# client.net
KiCad netlist of a schematic drawn in EAGLE
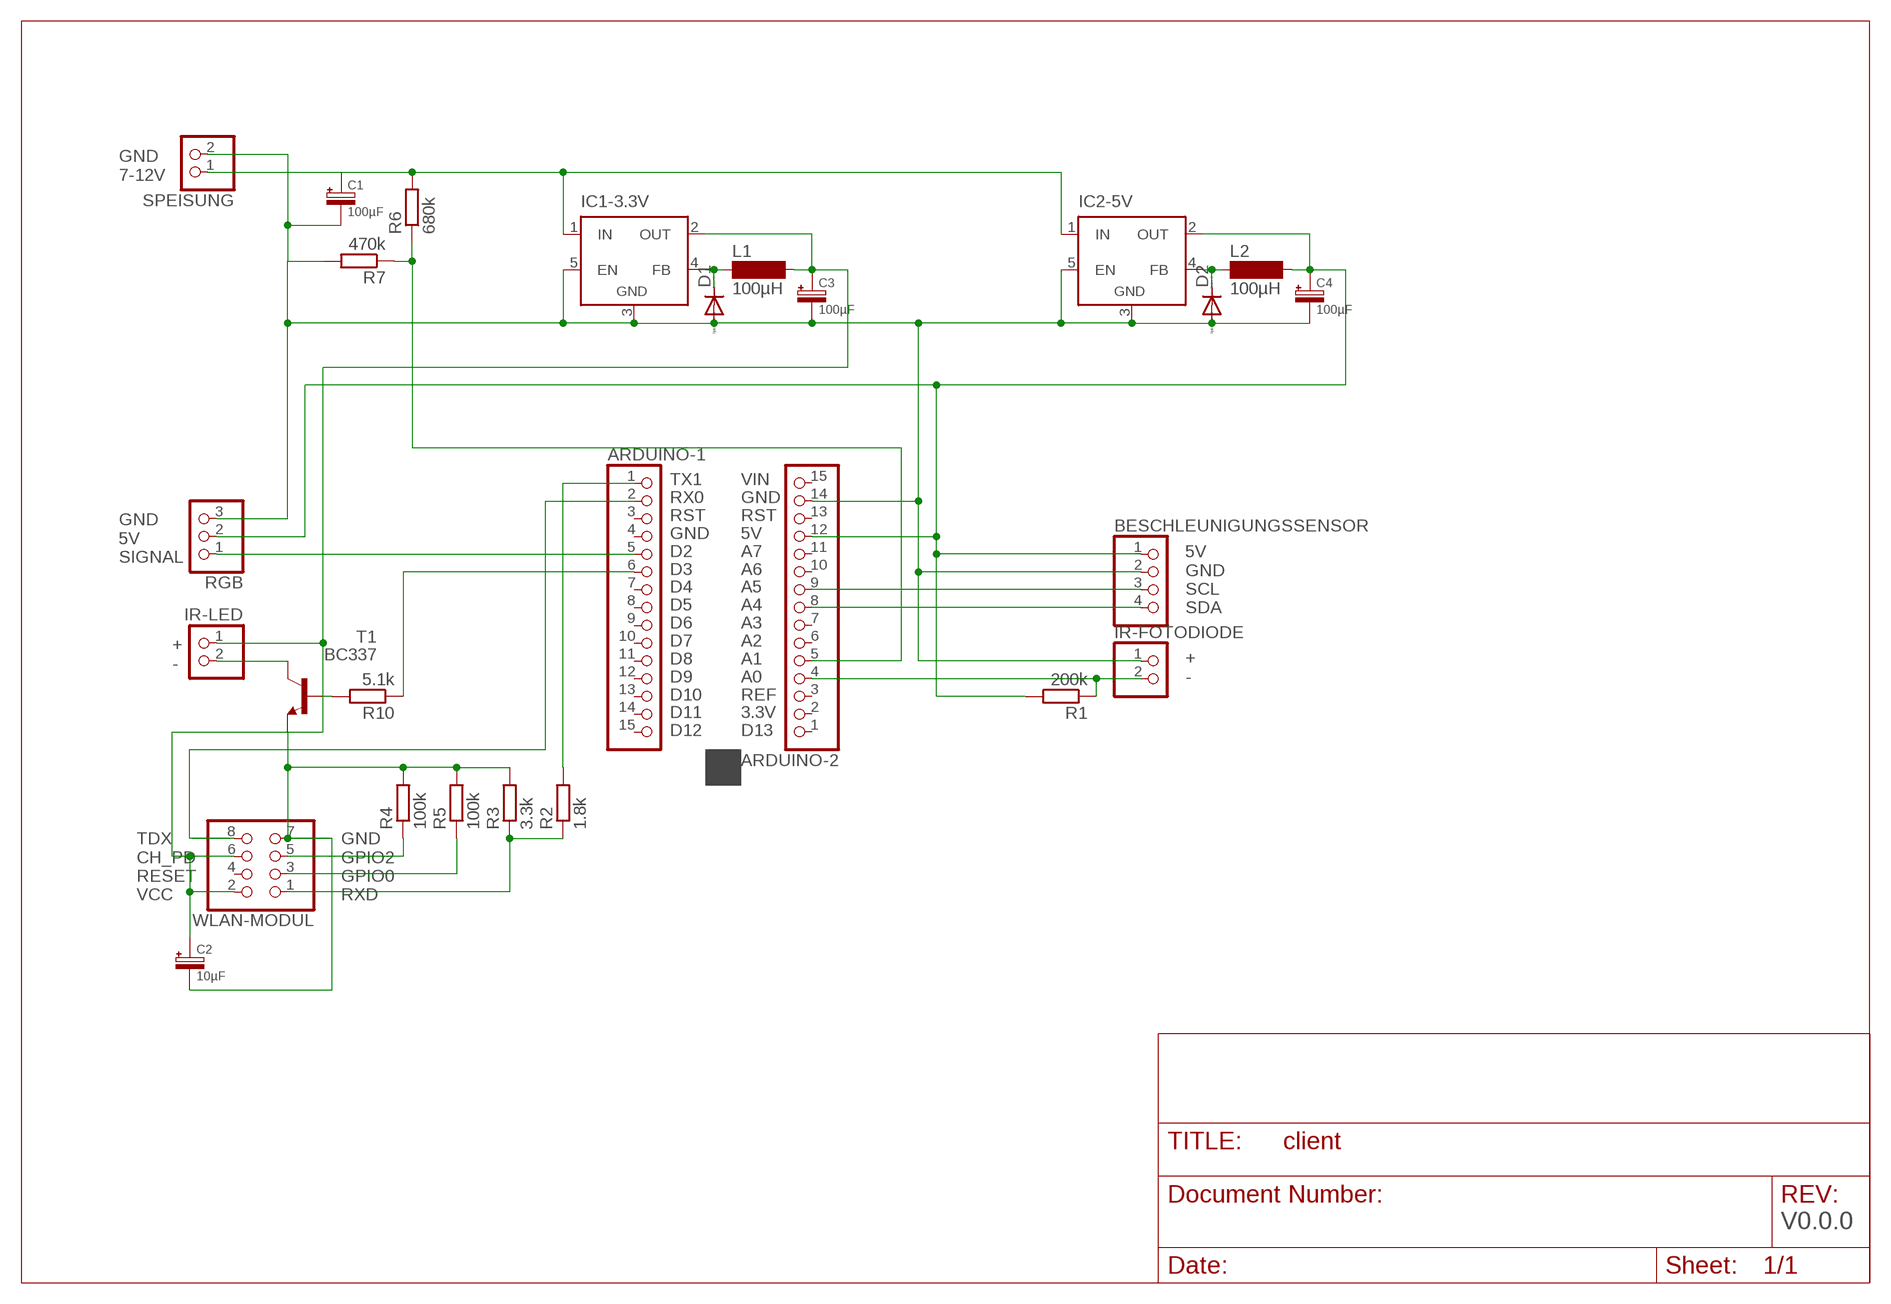
[diagram p0: schematic, sheet 1]

(export (version "E")
  (design (tool "Eeschema 10.0.6"))
  (components
    (comp (ref "ARDUINO-1")
      (value "PINHD-1X15")
      (footprint "eagle-import:1X15")
      (libsource (lib "eagle-import") (part "PINHD-1X15"))
    )
    (comp (ref "ARDUINO-2")
      (value "PINHD-1X15")
      (footprint "eagle-import:1X15")
      (libsource (lib "eagle-import") (part "PINHD-1X15"))
    )
    (comp (ref "BESCHLEUNIGUNGSSENSOR")
      (value "PINHD-1X4")
      (footprint "eagle-import:1X04")
      (libsource (lib "eagle-import") (part "PINHD-1X4"))
    )
    (comp (ref "C1")
      (value "100µF")
      (footprint "eagle-import:KONDENSATOR_ELEKTROLYT")
      (libsource (lib "eagle-import") (part "KONDENSATOR_ELEKTROLYT"))
    )
    (comp (ref "C2")
      (value "10µF")
      (footprint "eagle-import:KONDENSATOR_ELEKTROLYT")
      (libsource (lib "eagle-import") (part "KONDENSATOR_ELEKTROLYT"))
    )
    (comp (ref "C3")
      (value "100µF")
      (footprint "eagle-import:KONDENSATOR_ELEKTROLYT")
      (libsource (lib "eagle-import") (part "KONDENSATOR_ELEKTROLYT"))
    )
    (comp (ref "C4")
      (value "100µF")
      (footprint "eagle-import:KONDENSATOR_ELEKTROLYT")
      (libsource (lib "eagle-import") (part "KONDENSATOR_ELEKTROLYT"))
    )
    (comp (ref "D1")
      (value "DIODE-D-2.5")
      (footprint "eagle-import:D-2.5")
      (libsource (lib "eagle-import") (part "DIODE-D-2.5"))
    )
    (comp (ref "D2")
      (value "DIODE-D-2.5")
      (footprint "eagle-import:D-2.5")
      (libsource (lib "eagle-import") (part "DIODE-D-2.5"))
    )
    (comp (ref "IC1-3.3V")
      (value "LM2596TV")
      (footprint "eagle-import:TO220-51")
      (libsource (lib "eagle-import") (part "LM2596TV"))
    )
    (comp (ref "IC2-5V")
      (value "LM2596TV")
      (footprint "eagle-import:TO220-51")
      (libsource (lib "eagle-import") (part "LM2596TV"))
    )
    (comp (ref "IR-FOTODIODE")
      (value "PINHD-1X2")
      (footprint "eagle-import:1X02")
      (libsource (lib "eagle-import") (part "PINHD-1X2"))
    )
    (comp (ref "IR-LED")
      (value "PINHD-1X2")
      (footprint "eagle-import:1X02")
      (libsource (lib "eagle-import") (part "PINHD-1X2"))
    )
    (comp (ref "L1")
      (value "100µH")
      (footprint "eagle-import:SM-L15A")
      (libsource (lib "eagle-import") (part "SM-L15A"))
    )
    (comp (ref "L2")
      (value "100µH")
      (footprint "eagle-import:SM-L15A")
      (libsource (lib "eagle-import") (part "SM-L15A"))
    )
    (comp (ref "R1")
      (value "200k")
      (footprint "eagle-import:0204V")
      (libsource (lib "eagle-import") (part "rcl_334_R-EU_0204/2V"))
    )
    (comp (ref "R2")
      (value "1.8k")
      (footprint "eagle-import:0207_10")
      (libsource (lib "eagle-import") (part "R-EU_0207/10"))
    )
    (comp (ref "R3")
      (value "3.3k")
      (footprint "eagle-import:0207_10")
      (libsource (lib "eagle-import") (part "R-EU_0207/10"))
    )
    (comp (ref "R4")
      (value "100k")
      (footprint "eagle-import:0207_10")
      (libsource (lib "eagle-import") (part "R-EU_0207/10"))
    )
    (comp (ref "R5")
      (value "100k")
      (footprint "eagle-import:0207_10")
      (libsource (lib "eagle-import") (part "R-EU_0207/10"))
    )
    (comp (ref "R6")
      (value "680k")
      (footprint "eagle-import:0204V")
      (libsource (lib "eagle-import") (part "rcl_334_R-EU_0204/2V"))
    )
    (comp (ref "R7")
      (value "470k")
      (footprint "eagle-import:0204V")
      (libsource (lib "eagle-import") (part "rcl_334_R-EU_0204/2V"))
    )
    (comp (ref "R10")
      (value "5.1k")
      (footprint "eagle-import:0204V")
      (libsource (lib "eagle-import") (part "resistor_R-EU_0204/2V"))
    )
    (comp (ref "RGB")
      (value "PINHD-1X3")
      (footprint "eagle-import:1X03")
      (libsource (lib "eagle-import") (part "PINHD-1X3"))
    )
    (comp (ref "SPEISUNG")
      (value "PINHD-1X2")
      (footprint "eagle-import:1X02")
      (libsource (lib "eagle-import") (part "PINHD-1X2"))
    )
    (comp (ref "T1")
      (value "BC337")
      (footprint "eagle-import:TO92")
      (libsource (lib "eagle-import") (part "BC337"))
    )
    (comp (ref "WLAN-MODUL")
      (value "PINHD-2X4")
      (footprint "eagle-import:2X04")
      (libsource (lib "eagle-import") (part "PINHD-2X4"))
    )
  )
  (nets
    (net (code "1") (name "Net-(ARDUINO-1-Pad1)") (class "Default")
      (node (ref "ARDUINO-1") (pin "1") (pinfunction "1_1") (pintype "passive"))
      (node (ref "R2") (pin "2") (pinfunction "2_2") (pintype "passive"))
    )
    (net (code "2") (name "Net-(ARDUINO-1-Pad2)") (class "Default")
      (node (ref "ARDUINO-1") (pin "2") (pinfunction "2_2") (pintype "passive"))
      (node (ref "WLAN-MODUL") (pin "8") (pinfunction "8_8") (pintype "passive"))
    )
    (net (code "3") (name "Net-(ARDUINO-1-Pad5)") (class "Default")
      (node (ref "ARDUINO-1") (pin "5") (pinfunction "5_5") (pintype "passive"))
      (node (ref "RGB") (pin "1") (pinfunction "1_1") (pintype "passive"))
    )
    (net (code "4") (name "Net-(ARDUINO-1-Pad6)") (class "Default")
      (node (ref "ARDUINO-1") (pin "6") (pinfunction "6_6") (pintype "passive"))
      (node (ref "R10") (pin "1") (pinfunction "1_1") (pintype "passive"))
    )
    (net (code "5") (name "Net-(ARDUINO-2-Pad4)") (class "Default")
      (node (ref "ARDUINO-2") (pin "4") (pinfunction "4_4") (pintype "passive"))
      (node (ref "IR-FOTODIODE") (pin "2") (pinfunction "2_2") (pintype "passive"))
      (node (ref "R1") (pin "1") (pinfunction "1_1") (pintype "passive"))
    )
    (net (code "6") (name "Net-(ARDUINO-2-Pad5)") (class "Default")
      (node (ref "ARDUINO-2") (pin "5") (pinfunction "5_5") (pintype "passive"))
      (node (ref "R6") (pin "1") (pinfunction "1_1") (pintype "passive"))
      (node (ref "R7") (pin "1") (pinfunction "1_1") (pintype "passive"))
    )
    (net (code "7") (name "Net-(ARDUINO-2-Pad8)") (class "Default")
      (node (ref "ARDUINO-2") (pin "8") (pinfunction "8_8") (pintype "passive"))
      (node (ref "BESCHLEUNIGUNGSSENSOR") (pin "4") (pinfunction "4_4") (pintype "passive"))
    )
    (net (code "8") (name "Net-(ARDUINO-2-Pad9)") (class "Default")
      (node (ref "ARDUINO-2") (pin "9") (pinfunction "9_9") (pintype "passive"))
      (node (ref "BESCHLEUNIGUNGSSENSOR") (pin "3") (pinfunction "3_3") (pintype "passive"))
    )
    (net (code "9") (name "Net-(IC1-3.3V-EN)") (class "Default")
      (node (ref "ARDUINO-2") (pin "14") (pinfunction "14_14") (pintype "passive"))
      (node (ref "BESCHLEUNIGUNGSSENSOR") (pin "2") (pinfunction "2_2") (pintype "passive"))
      (node (ref "C1") (pin "P$1") (pinfunction "P$1_P$1") (pintype "passive"))
      (node (ref "C3") (pin "P$1") (pinfunction "P$1_P$1") (pintype "passive"))
      (node (ref "C4") (pin "P$1") (pinfunction "P$1_P$1") (pintype "passive"))
      (node (ref "D1") (pin "A") (pinfunction "A_A") (pintype "passive"))
      (node (ref "D2") (pin "A") (pinfunction "A_A") (pintype "passive"))
      (node (ref "IC1-3.3V") (pin "3") (pinfunction "GND_3") (pintype "power_in"))
      (node (ref "IC1-3.3V") (pin "5") (pinfunction "EN_5") (pintype "input"))
      (node (ref "IC2-5V") (pin "3") (pinfunction "GND_3") (pintype "power_in"))
      (node (ref "IC2-5V") (pin "5") (pinfunction "EN_5") (pintype "input"))
      (node (ref "IR-FOTODIODE") (pin "1") (pinfunction "1_1") (pintype "passive"))
      (node (ref "R7") (pin "2") (pinfunction "2_2") (pintype "passive"))
      (node (ref "RGB") (pin "3") (pinfunction "3_3") (pintype "passive"))
      (node (ref "SPEISUNG") (pin "2") (pinfunction "2_2") (pintype "passive"))
    )
    (net (code "10") (name "Net-(IC1-3.3V-FB)") (class "Default")
      (node (ref "D1") (pin "C") (pinfunction "C_C") (pintype "passive"))
      (node (ref "IC1-3.3V") (pin "4") (pinfunction "FB_4") (pintype "input"))
      (node (ref "L1") (pin "1") (pinfunction "1_1") (pintype "passive"))
    )
    (net (code "11") (name "Net-(IC1-3.3V-IN)") (class "Default")
      (node (ref "C1") (pin "P$2") (pinfunction "P$2_P$2") (pintype "passive"))
      (node (ref "IC1-3.3V") (pin "1") (pinfunction "IN_1") (pintype "input"))
      (node (ref "IC2-5V") (pin "1") (pinfunction "IN_1") (pintype "input"))
      (node (ref "R6") (pin "2") (pinfunction "2_2") (pintype "passive"))
      (node (ref "SPEISUNG") (pin "1") (pinfunction "1_1") (pintype "passive"))
    )
    (net (code "12") (name "Net-(IC1-3.3V-OUT)") (class "Default")
      (node (ref "C2") (pin "P$2") (pinfunction "P$2_P$2") (pintype "passive"))
      (node (ref "C3") (pin "P$2") (pinfunction "P$2_P$2") (pintype "passive"))
      (node (ref "IC1-3.3V") (pin "2") (pinfunction "OUT_2") (pintype "output"))
      (node (ref "IR-LED") (pin "1") (pinfunction "1_1") (pintype "passive"))
      (node (ref "L1") (pin "2") (pinfunction "2_2") (pintype "passive"))
      (node (ref "WLAN-MODUL") (pin "2") (pinfunction "2_2") (pintype "passive"))
      (node (ref "WLAN-MODUL") (pin "6") (pinfunction "6_6") (pintype "passive"))
    )
    (net (code "13") (name "Net-(IC2-5V-FB)") (class "Default")
      (node (ref "D2") (pin "C") (pinfunction "C_C") (pintype "passive"))
      (node (ref "IC2-5V") (pin "4") (pinfunction "FB_4") (pintype "input"))
      (node (ref "L2") (pin "1") (pinfunction "1_1") (pintype "passive"))
    )
    (net (code "14") (name "Net-(IC2-5V-OUT)") (class "Default")
      (node (ref "ARDUINO-2") (pin "12") (pinfunction "12_12") (pintype "passive"))
      (node (ref "BESCHLEUNIGUNGSSENSOR") (pin "1") (pinfunction "1_1") (pintype "passive"))
      (node (ref "C4") (pin "P$2") (pinfunction "P$2_P$2") (pintype "passive"))
      (node (ref "IC2-5V") (pin "2") (pinfunction "OUT_2") (pintype "output"))
      (node (ref "L2") (pin "2") (pinfunction "2_2") (pintype "passive"))
      (node (ref "R1") (pin "2") (pinfunction "2_2") (pintype "passive"))
      (node (ref "RGB") (pin "2") (pinfunction "2_2") (pintype "passive"))
    )
    (net (code "15") (name "Net-(R2-Pad1)") (class "Default")
      (node (ref "R2") (pin "1") (pinfunction "1_1") (pintype "passive"))
      (node (ref "R3") (pin "1") (pinfunction "1_1") (pintype "passive"))
      (node (ref "WLAN-MODUL") (pin "1") (pinfunction "1_1") (pintype "passive"))
    )
    (net (code "16") (name "Net-(R4-Pad1)") (class "Default")
      (node (ref "R4") (pin "1") (pinfunction "1_1") (pintype "passive"))
      (node (ref "WLAN-MODUL") (pin "5") (pinfunction "5_5") (pintype "passive"))
    )
    (net (code "17") (name "Net-(R5-Pad1)") (class "Default")
      (node (ref "R5") (pin "1") (pinfunction "1_1") (pintype "passive"))
      (node (ref "WLAN-MODUL") (pin "3") (pinfunction "3_3") (pintype "passive"))
    )
    (net (code "18") (name "Net-(T1-B)") (class "Default")
      (node (ref "R10") (pin "2") (pinfunction "2_2") (pintype "passive"))
      (node (ref "T1") (pin "2") (pinfunction "B_2") (pintype "passive"))
    )
    (net (code "19") (name "Net-(T1-C)") (class "Default")
      (node (ref "IR-LED") (pin "2") (pinfunction "2_2") (pintype "passive"))
      (node (ref "T1") (pin "3") (pinfunction "C_3") (pintype "passive"))
    )
    (net (code "20") (name "Net-(T1-E)") (class "Default")
      (node (ref "C2") (pin "P$1") (pinfunction "P$1_P$1") (pintype "passive"))
      (node (ref "R3") (pin "2") (pinfunction "2_2") (pintype "passive"))
      (node (ref "R4") (pin "2") (pinfunction "2_2") (pintype "passive"))
      (node (ref "R5") (pin "2") (pinfunction "2_2") (pintype "passive"))
      (node (ref "T1") (pin "1") (pinfunction "E_1") (pintype "passive"))
      (node (ref "WLAN-MODUL") (pin "7") (pinfunction "7_7") (pintype "passive"))
    )
    (net (code "21") (name "unconnected-(ARDUINO-1-Pad3)") (class "Default")
      (node (ref "ARDUINO-1") (pin "3") (pinfunction "3_3") (pintype "passive"))
    )
    (net (code "22") (name "unconnected-(ARDUINO-1-Pad4)") (class "Default")
      (node (ref "ARDUINO-1") (pin "4") (pinfunction "4_4") (pintype "passive"))
    )
    (net (code "23") (name "unconnected-(ARDUINO-1-Pad7)") (class "Default")
      (node (ref "ARDUINO-1") (pin "7") (pinfunction "7_7") (pintype "passive"))
    )
    (net (code "24") (name "unconnected-(ARDUINO-1-Pad8)") (class "Default")
      (node (ref "ARDUINO-1") (pin "8") (pinfunction "8_8") (pintype "passive"))
    )
    (net (code "25") (name "unconnected-(ARDUINO-1-Pad9)") (class "Default")
      (node (ref "ARDUINO-1") (pin "9") (pinfunction "9_9") (pintype "passive"))
    )
    (net (code "26") (name "unconnected-(ARDUINO-1-Pad10)") (class "Default")
      (node (ref "ARDUINO-1") (pin "10") (pinfunction "10_10") (pintype "passive"))
    )
    (net (code "27") (name "unconnected-(ARDUINO-1-Pad11)") (class "Default")
      (node (ref "ARDUINO-1") (pin "11") (pinfunction "11_11") (pintype "passive"))
    )
    (net (code "28") (name "unconnected-(ARDUINO-1-Pad12)") (class "Default")
      (node (ref "ARDUINO-1") (pin "12") (pinfunction "12_12") (pintype "passive"))
    )
    (net (code "29") (name "unconnected-(ARDUINO-1-Pad13)") (class "Default")
      (node (ref "ARDUINO-1") (pin "13") (pinfunction "13_13") (pintype "passive"))
    )
    (net (code "30") (name "unconnected-(ARDUINO-1-Pad14)") (class "Default")
      (node (ref "ARDUINO-1") (pin "14") (pinfunction "14_14") (pintype "passive"))
    )
    (net (code "31") (name "unconnected-(ARDUINO-1-Pad15)") (class "Default")
      (node (ref "ARDUINO-1") (pin "15") (pinfunction "15_15") (pintype "passive"))
    )
    (net (code "32") (name "unconnected-(ARDUINO-2-Pad1)") (class "Default")
      (node (ref "ARDUINO-2") (pin "1") (pinfunction "1_1") (pintype "passive"))
    )
    (net (code "33") (name "unconnected-(ARDUINO-2-Pad2)") (class "Default")
      (node (ref "ARDUINO-2") (pin "2") (pinfunction "2_2") (pintype "passive"))
    )
    (net (code "34") (name "unconnected-(ARDUINO-2-Pad3)") (class "Default")
      (node (ref "ARDUINO-2") (pin "3") (pinfunction "3_3") (pintype "passive"))
    )
    (net (code "35") (name "unconnected-(ARDUINO-2-Pad6)") (class "Default")
      (node (ref "ARDUINO-2") (pin "6") (pinfunction "6_6") (pintype "passive"))
    )
    (net (code "36") (name "unconnected-(ARDUINO-2-Pad7)") (class "Default")
      (node (ref "ARDUINO-2") (pin "7") (pinfunction "7_7") (pintype "passive"))
    )
    (net (code "37") (name "unconnected-(ARDUINO-2-Pad10)") (class "Default")
      (node (ref "ARDUINO-2") (pin "10") (pinfunction "10_10") (pintype "passive"))
    )
    (net (code "38") (name "unconnected-(ARDUINO-2-Pad11)") (class "Default")
      (node (ref "ARDUINO-2") (pin "11") (pinfunction "11_11") (pintype "passive"))
    )
    (net (code "39") (name "unconnected-(ARDUINO-2-Pad13)") (class "Default")
      (node (ref "ARDUINO-2") (pin "13") (pinfunction "13_13") (pintype "passive"))
    )
    (net (code "40") (name "unconnected-(ARDUINO-2-Pad15)") (class "Default")
      (node (ref "ARDUINO-2") (pin "15") (pinfunction "15_15") (pintype "passive"))
    )
    (net (code "41") (name "unconnected-(WLAN-MODUL-Pad4)") (class "Default")
      (node (ref "WLAN-MODUL") (pin "4") (pinfunction "4_4") (pintype "passive"))
    )
  )
)
